# pc_kalam_sense_cap.net
KiCad netlist of a schematic drawn in EAGLE
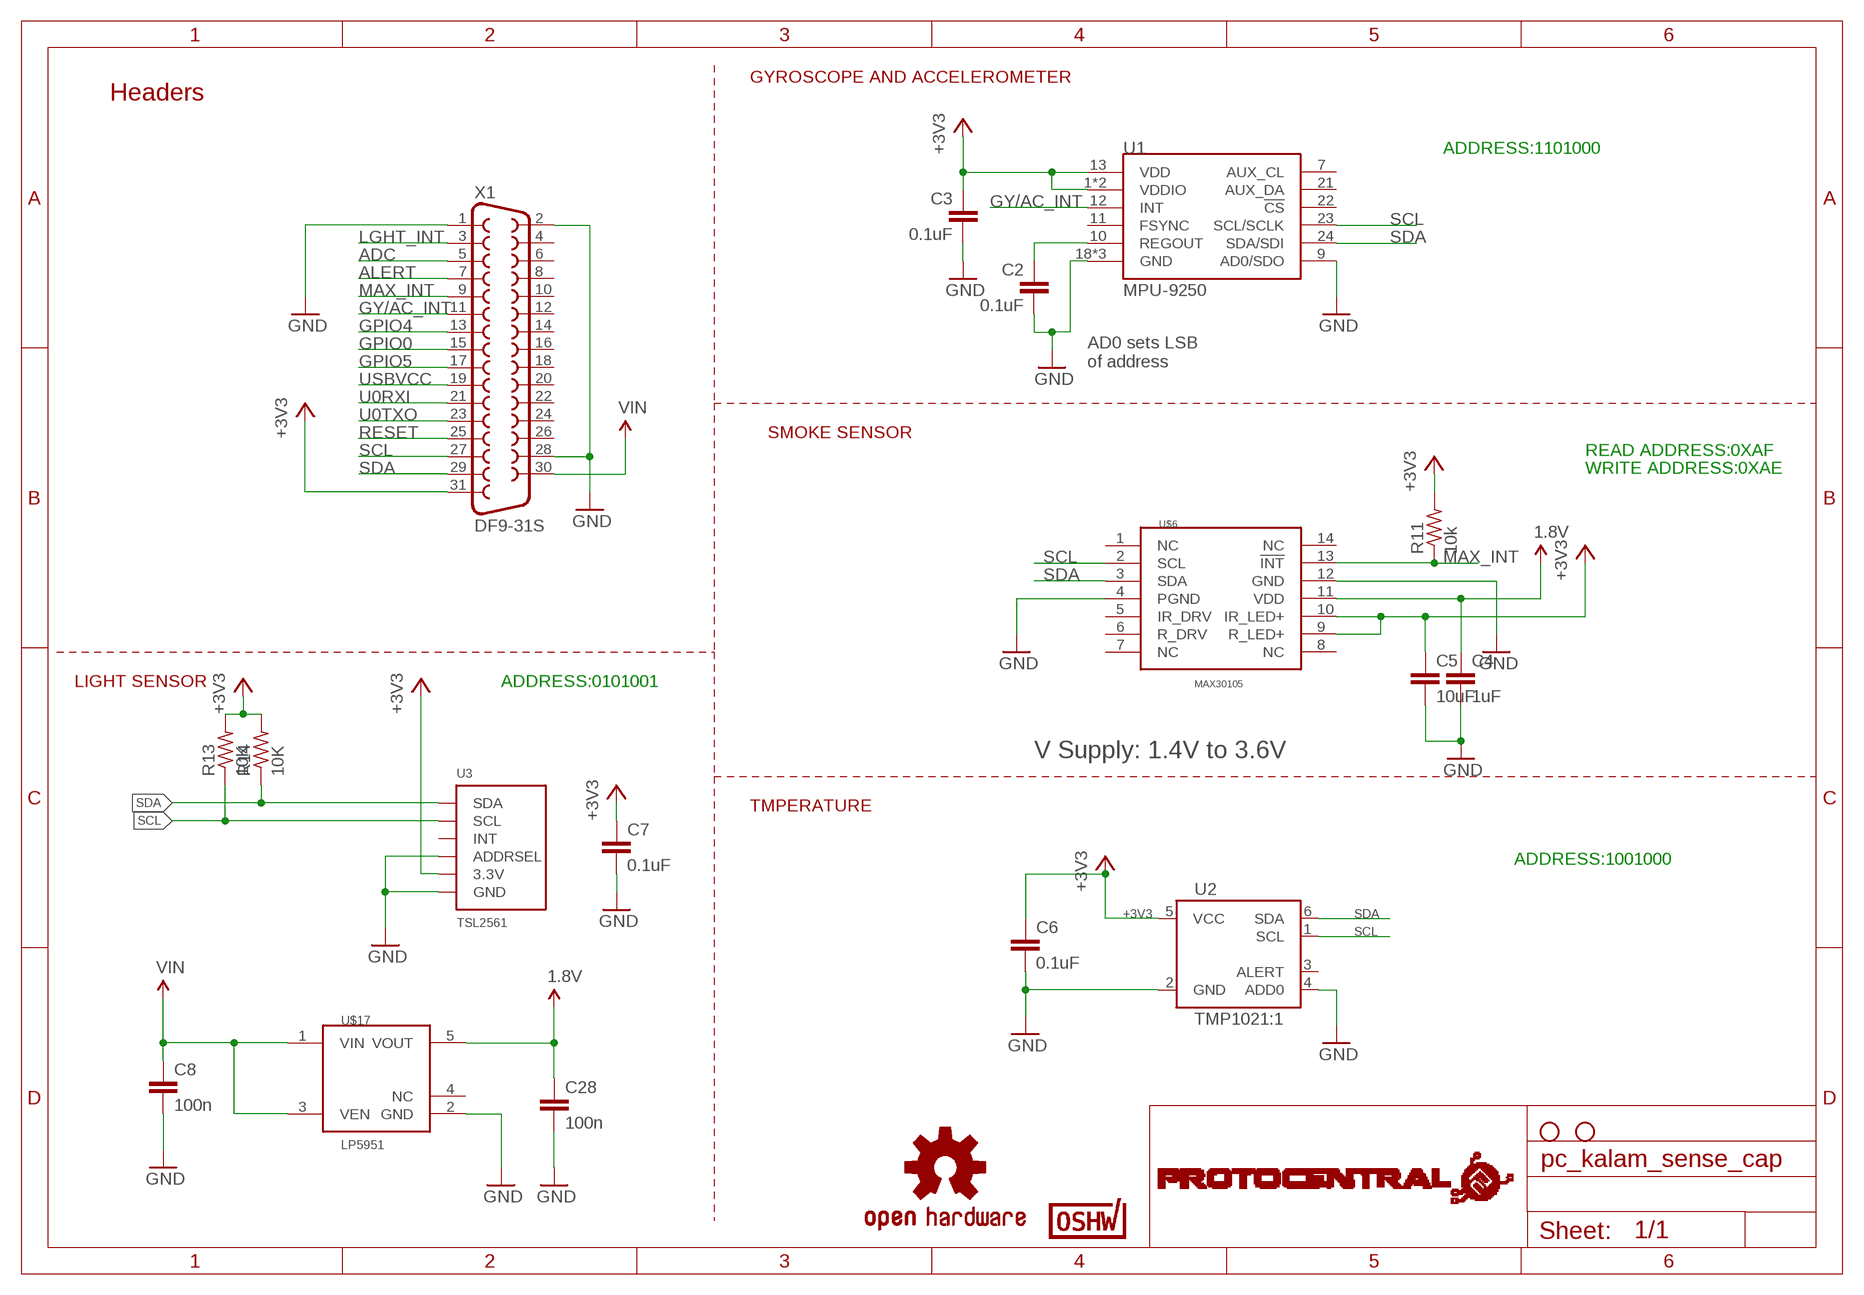
[diagram p0: schematic, sheet 1]

(export (version "E")
  (design (tool "Eeschema 10.0.6"))
  (components
    (comp (ref "C2")
      (value "0.1uF")
      (footprint "eagle-import:0603-CAP")
      (libsource (lib "eagle-import") (part "0.1UF-25V(+80/-20%)(0603)"))
    )
    (comp (ref "C3")
      (value "0.1uF")
      (footprint "eagle-import:0603-CAP")
      (libsource (lib "eagle-import") (part "0.1UF-25V(+80/-20%)(0603)"))
    )
    (comp (ref "C4")
      (value "1uF")
      (footprint "eagle-import:C0805")
      (libsource (lib "eagle-import") (part "C-EUC0805"))
    )
    (comp (ref "C5")
      (value "10uF")
      (footprint "eagle-import:C0805")
      (libsource (lib "eagle-import") (part "C-EUC0805"))
    )
    (comp (ref "C6")
      (value "0.1uF")
      (footprint "eagle-import:0603-CAP")
      (libsource (lib "eagle-import") (part "CAP0603-CAP"))
    )
    (comp (ref "C7")
      (value "0.1uF")
      (footprint "eagle-import:C0805")
      (libsource (lib "eagle-import") (part "C-EUC0805"))
    )
    (comp (ref "C8")
      (value "100n")
      (footprint "eagle-import:C0402")
      (libsource (lib "eagle-import") (part "C-EUC0402"))
    )
    (comp (ref "C28")
      (value "100n")
      (footprint "eagle-import:C0402")
      (libsource (lib "eagle-import") (part "C-EUC0402"))
    )
    (comp (ref "R11")
      (value "10k")
      (footprint "eagle-import:R0402")
      (libsource (lib "eagle-import") (part "R-US_R0402"))
    )
    (comp (ref "R13")
      (value "10K")
      (footprint "eagle-import:R0805")
      (libsource (lib "eagle-import") (part "R-US_R0805"))
    )
    (comp (ref "R14")
      (value "10K")
      (footprint "eagle-import:R0805")
      (libsource (lib "eagle-import") (part "R-US_R0805"))
    )
    (comp (ref "STANDOFF7")
      (value "STAND-OFF")
      (footprint "eagle-import:STAND-OFF")
      (libsource (lib "eagle-import") (part "STAND-OFF"))
    )
    (comp (ref "STANDOFF8")
      (value "STAND-OFF")
      (footprint "eagle-import:STAND-OFF")
      (libsource (lib "eagle-import") (part "STAND-OFF"))
    )
    (comp (ref "U$2")
      (value "CERT-SMALL")
      (footprint "eagle-import:CERT-SMALL-SILK")
      (libsource (lib "eagle-import") (part "CERT-SMALL"))
    )
    (comp (ref "U$3")
      (value "OSHW-LOGOS")
      (footprint "eagle-import:OSHW-LOGO-S")
      (libsource (lib "eagle-import") (part "OSHW-LOGOS"))
    )
    (comp (ref "U$6")
      (value "MAX30105")
      (footprint "eagle-import:OESIP-14")
      (libsource (lib "eagle-import") (part "MAX30100"))
    )
    (comp (ref "U$9")
      (value "PROTY_LOGO_WITH_TEXT")
      (footprint "eagle-import:PROTY_WITH_TEXT")
      (libsource (lib "eagle-import") (part "PROTY_LOGO_WITH_TEXT"))
    )
    (comp (ref "U$17")
      (value "LP5951")
      (footprint "eagle-import:SC70-5")
      (libsource (lib "eagle-import") (part "LP5951"))
    )
    (comp (ref "U1")
      (value "MPU-9250")
      (footprint "eagle-import:QFN24_PAD")
      (libsource (lib "eagle-import") (part "MPU-9250"))
    )
    (comp (ref "U2")
      (value "TMP1021:1")
      (footprint "eagle-import:SOT563-2")
      (libsource (lib "eagle-import") (part "TMP1021{colon}1"))
    )
    (comp (ref "U3")
      (value "TSL2561")
      (footprint "eagle-import:TSL2561_FN")
      (libsource (lib "eagle-import") (part "TSL2561"))
    )
    (comp (ref "X1")
      (value "DF9-31S")
      (footprint "eagle-import:DF9-31S")
      (fields (field (name "MPN") "DF9-31S-1V(32)"))
      (libsource (lib "eagle-import") (part "DF9-31S"))
    )
  )
  (nets
    (net (code "1") (name "+3V3") (class "Default")
      (node (ref "C3") (pin "1") (pinfunction "1_1") (pintype "passive"))
      (node (ref "C5") (pin "1") (pinfunction "1_1") (pintype "passive"))
      (node (ref "C6") (pin "1") (pinfunction "1_1") (pintype "passive"))
      (node (ref "C7") (pin "1") (pinfunction "1_1") (pintype "passive"))
      (node (ref "R11") (pin "2") (pinfunction "2_2") (pintype "passive"))
      (node (ref "R13") (pin "2") (pinfunction "2_2") (pintype "passive"))
      (node (ref "R14") (pin "2") (pinfunction "2_2") (pintype "passive"))
      (node (ref "U$6") (pin "10") (pinfunction "IR_LED+_10") (pintype "bidirectional"))
      (node (ref "U$6") (pin "9") (pinfunction "R_LED+_9") (pintype "bidirectional"))
      (node (ref "U1") (pin "1") (pinfunction "VDDIO_1") (pintype "bidirectional"))
      (node (ref "U1") (pin "13") (pinfunction "VDD_13") (pintype "bidirectional"))
      (node (ref "U1") (pin "8") (pinfunction "VDDIO_8") (pintype "bidirectional"))
      (node (ref "U2") (pin "5") (pinfunction "VCC_5") (pintype "bidirectional"))
      (node (ref "U3") (pin "VDD") (pinfunction "3.3V_VDD") (pintype "bidirectional"))
      (node (ref "X1") (pin "31") (pinfunction "31_31") (pintype "passive"))
    )
    (net (code "2") (name "/ADC") (class "Default")
      (node (ref "X1") (pin "5") (pinfunction "5_5") (pintype "passive"))
    )
    (net (code "3") (name "/ALERT") (class "Default")
      (node (ref "X1") (pin "7") (pinfunction "7_7") (pintype "passive"))
    )
    (net (code "4") (name "/GPIO0") (class "Default")
      (node (ref "X1") (pin "15") (pinfunction "15_15") (pintype "passive"))
    )
    (net (code "5") (name "/GPIO4") (class "Default")
      (node (ref "X1") (pin "13") (pinfunction "13_13") (pintype "passive"))
    )
    (net (code "6") (name "/GPIO5") (class "Default")
      (node (ref "X1") (pin "17") (pinfunction "17_17") (pintype "passive"))
    )
    (net (code "7") (name "/GY{slash}AC_INT") (class "Default")
      (node (ref "U1") (pin "12") (pinfunction "INT_12") (pintype "bidirectional"))
      (node (ref "X1") (pin "11") (pinfunction "11_11") (pintype "passive"))
    )
    (net (code "8") (name "/LGHT_INT") (class "Default")
      (node (ref "X1") (pin "3") (pinfunction "3_3") (pintype "passive"))
    )
    (net (code "9") (name "/MAX_INT") (class "Default")
      (node (ref "R11") (pin "1") (pinfunction "1_1") (pintype "passive"))
      (node (ref "U$6") (pin "13") (pinfunction "~{INT}_13") (pintype "bidirectional"))
      (node (ref "X1") (pin "9") (pinfunction "9_9") (pintype "passive"))
    )
    (net (code "10") (name "/RESET") (class "Default")
      (node (ref "X1") (pin "25") (pinfunction "25_25") (pintype "passive"))
    )
    (net (code "11") (name "/U0RXI") (class "Default")
      (node (ref "X1") (pin "21") (pinfunction "21_21") (pintype "passive"))
    )
    (net (code "12") (name "/U0TXO") (class "Default")
      (node (ref "X1") (pin "23") (pinfunction "23_23") (pintype "passive"))
    )
    (net (code "13") (name "/USBVCC") (class "Default")
      (node (ref "X1") (pin "19") (pinfunction "19_19") (pintype "passive"))
    )
    (net (code "14") (name "1.8V") (class "Default")
      (node (ref "C28") (pin "1") (pinfunction "1_1") (pintype "passive"))
      (node (ref "C4") (pin "1") (pinfunction "1_1") (pintype "passive"))
      (node (ref "U$17") (pin "5") (pinfunction "VOUT_5") (pintype "bidirectional"))
      (node (ref "U$6") (pin "11") (pinfunction "VDD_11") (pintype "bidirectional"))
    )
    (net (code "15") (name "GND") (class "Default")
      (node (ref "C2") (pin "2") (pinfunction "2_2") (pintype "passive"))
      (node (ref "C28") (pin "2") (pinfunction "2_2") (pintype "passive"))
      (node (ref "C3") (pin "2") (pinfunction "2_2") (pintype "passive"))
      (node (ref "C4") (pin "2") (pinfunction "2_2") (pintype "passive"))
      (node (ref "C5") (pin "2") (pinfunction "2_2") (pintype "passive"))
      (node (ref "C6") (pin "2") (pinfunction "2_2") (pintype "passive"))
      (node (ref "C7") (pin "2") (pinfunction "2_2") (pintype "passive"))
      (node (ref "C8") (pin "2") (pinfunction "2_2") (pintype "passive"))
      (node (ref "U$17") (pin "2") (pinfunction "GND_2") (pintype "bidirectional"))
      (node (ref "U$6") (pin "12") (pinfunction "GND_12") (pintype "bidirectional"))
      (node (ref "U$6") (pin "4") (pinfunction "PGND_4") (pintype "bidirectional"))
      (node (ref "U1") (pin "18") (pinfunction "GND_18") (pintype "bidirectional"))
      (node (ref "U1") (pin "20") (pinfunction "GND_20") (pintype "bidirectional"))
      (node (ref "U1") (pin "9") (pinfunction "AD0/SDO_9") (pintype "bidirectional"))
      (node (ref "U1") (pin "CENTER") (pinfunction "GND_CENTER") (pintype "bidirectional"))
      (node (ref "U2") (pin "2") (pinfunction "GND_2") (pintype "bidirectional"))
      (node (ref "U2") (pin "4") (pinfunction "ADD0_4") (pintype "bidirectional"))
      (node (ref "U3") (pin "ADR") (pinfunction "ADDRSEL_ADR") (pintype "bidirectional"))
      (node (ref "U3") (pin "VSS") (pinfunction "GND_VSS") (pintype "bidirectional"))
      (node (ref "X1") (pin "1") (pinfunction "1_1") (pintype "passive"))
      (node (ref "X1") (pin "2") (pinfunction "2_2") (pintype "passive"))
      (node (ref "X1") (pin "28") (pinfunction "28_28") (pintype "passive"))
    )
    (net (code "16") (name "Net-(U1-REGOUT)") (class "Default")
      (node (ref "C2") (pin "1") (pinfunction "1_1") (pintype "passive"))
      (node (ref "U1") (pin "10") (pinfunction "REGOUT_10") (pintype "bidirectional"))
    )
    (net (code "17") (name "SCL") (class "Default")
      (node (ref "R13") (pin "1") (pinfunction "1_1") (pintype "passive"))
      (node (ref "U$6") (pin "2") (pinfunction "SCL_2") (pintype "bidirectional"))
      (node (ref "U1") (pin "23") (pinfunction "SCL/SCLK_23") (pintype "bidirectional"))
      (node (ref "U2") (pin "1") (pinfunction "SCL_1") (pintype "bidirectional"))
      (node (ref "U3") (pin "CLK") (pinfunction "SCL_CLK") (pintype "bidirectional"))
      (node (ref "X1") (pin "27") (pinfunction "27_27") (pintype "passive"))
    )
    (net (code "18") (name "SDA") (class "Default")
      (node (ref "R14") (pin "1") (pinfunction "1_1") (pintype "passive"))
      (node (ref "U$6") (pin "3") (pinfunction "SDA_3") (pintype "bidirectional"))
      (node (ref "U1") (pin "24") (pinfunction "SDA/SDI_24") (pintype "bidirectional"))
      (node (ref "U2") (pin "6") (pinfunction "SDA_6") (pintype "bidirectional"))
      (node (ref "U3") (pin "DATA") (pinfunction "SDA_DATA") (pintype "bidirectional"))
      (node (ref "X1") (pin "29") (pinfunction "29_29") (pintype "passive"))
    )
    (net (code "19") (name "VIN") (class "Default")
      (node (ref "C8") (pin "1") (pinfunction "1_1") (pintype "passive"))
      (node (ref "U$17") (pin "1") (pinfunction "VIN_1") (pintype "bidirectional"))
      (node (ref "U$17") (pin "3") (pinfunction "VEN_3") (pintype "bidirectional"))
      (node (ref "X1") (pin "30") (pinfunction "30_30") (pintype "passive"))
    )
    (net (code "20") (name "unconnected-(U$6-IR_DRV-Pad5)") (class "Default")
      (node (ref "U$6") (pin "5") (pinfunction "IR_DRV_5") (pintype "bidirectional"))
    )
    (net (code "21") (name "unconnected-(U$6-NC-Pad1)") (class "Default")
      (node (ref "U$6") (pin "1") (pinfunction "NC_1") (pintype "bidirectional"))
    )
    (net (code "22") (name "unconnected-(U$6-NC-Pad7)") (class "Default")
      (node (ref "U$6") (pin "7") (pinfunction "NC_7") (pintype "bidirectional"))
    )
    (net (code "23") (name "unconnected-(U$6-NC-Pad8)") (class "Default")
      (node (ref "U$6") (pin "8") (pinfunction "NC_8") (pintype "bidirectional"))
    )
    (net (code "24") (name "unconnected-(U$6-NC-Pad14)") (class "Default")
      (node (ref "U$6") (pin "14") (pinfunction "NC_14") (pintype "bidirectional"))
    )
    (net (code "25") (name "unconnected-(U$6-R_DRV-Pad6)") (class "Default")
      (node (ref "U$6") (pin "6") (pinfunction "R_DRV_6") (pintype "bidirectional"))
    )
    (net (code "26") (name "unconnected-(U$17-NC-Pad4)") (class "Default")
      (node (ref "U$17") (pin "4") (pinfunction "NC_4") (pintype "bidirectional"))
    )
    (net (code "27") (name "unconnected-(U1-AUX_CL-Pad7)") (class "Default")
      (node (ref "U1") (pin "7") (pinfunction "AUX_CL_7") (pintype "bidirectional"))
    )
    (net (code "28") (name "unconnected-(U1-AUX_DA-Pad21)") (class "Default")
      (node (ref "U1") (pin "21") (pinfunction "AUX_DA_21") (pintype "bidirectional"))
    )
    (net (code "29") (name "unconnected-(U1-FSYNC-Pad11)") (class "Default")
      (node (ref "U1") (pin "11") (pinfunction "FSYNC_11") (pintype "bidirectional"))
    )
    (net (code "30") (name "unconnected-(U1-~{CS}-Pad22)") (class "Default")
      (node (ref "U1") (pin "22") (pinfunction "~{CS}_22") (pintype "bidirectional"))
    )
    (net (code "31") (name "unconnected-(U2-ALERT-Pad3)") (class "Default")
      (node (ref "U2") (pin "3") (pinfunction "ALERT_3") (pintype "bidirectional"))
    )
    (net (code "32") (name "unconnected-(U3-PadINT)") (class "Default")
      (node (ref "U3") (pin "INT") (pinfunction "INT_INT") (pintype "bidirectional"))
    )
    (net (code "33") (name "unconnected-(X1-Pad4)") (class "Default")
      (node (ref "X1") (pin "4") (pinfunction "4_4") (pintype "passive"))
    )
    (net (code "34") (name "unconnected-(X1-Pad6)") (class "Default")
      (node (ref "X1") (pin "6") (pinfunction "6_6") (pintype "passive"))
    )
    (net (code "35") (name "unconnected-(X1-Pad8)") (class "Default")
      (node (ref "X1") (pin "8") (pinfunction "8_8") (pintype "passive"))
    )
    (net (code "36") (name "unconnected-(X1-Pad10)") (class "Default")
      (node (ref "X1") (pin "10") (pinfunction "10_10") (pintype "passive"))
    )
    (net (code "37") (name "unconnected-(X1-Pad12)") (class "Default")
      (node (ref "X1") (pin "12") (pinfunction "12_12") (pintype "passive"))
    )
    (net (code "38") (name "unconnected-(X1-Pad14)") (class "Default")
      (node (ref "X1") (pin "14") (pinfunction "14_14") (pintype "passive"))
    )
    (net (code "39") (name "unconnected-(X1-Pad16)") (class "Default")
      (node (ref "X1") (pin "16") (pinfunction "16_16") (pintype "passive"))
    )
    (net (code "40") (name "unconnected-(X1-Pad18)") (class "Default")
      (node (ref "X1") (pin "18") (pinfunction "18_18") (pintype "passive"))
    )
    (net (code "41") (name "unconnected-(X1-Pad20)") (class "Default")
      (node (ref "X1") (pin "20") (pinfunction "20_20") (pintype "passive"))
    )
    (net (code "42") (name "unconnected-(X1-Pad22)") (class "Default")
      (node (ref "X1") (pin "22") (pinfunction "22_22") (pintype "passive"))
    )
    (net (code "43") (name "unconnected-(X1-Pad24)") (class "Default")
      (node (ref "X1") (pin "24") (pinfunction "24_24") (pintype "passive"))
    )
    (net (code "44") (name "unconnected-(X1-Pad26)") (class "Default")
      (node (ref "X1") (pin "26") (pinfunction "26_26") (pintype "passive"))
    )
  )
)
